# HW_V5_0.net
KiCad netlist of a schematic drawn in Altium Designer
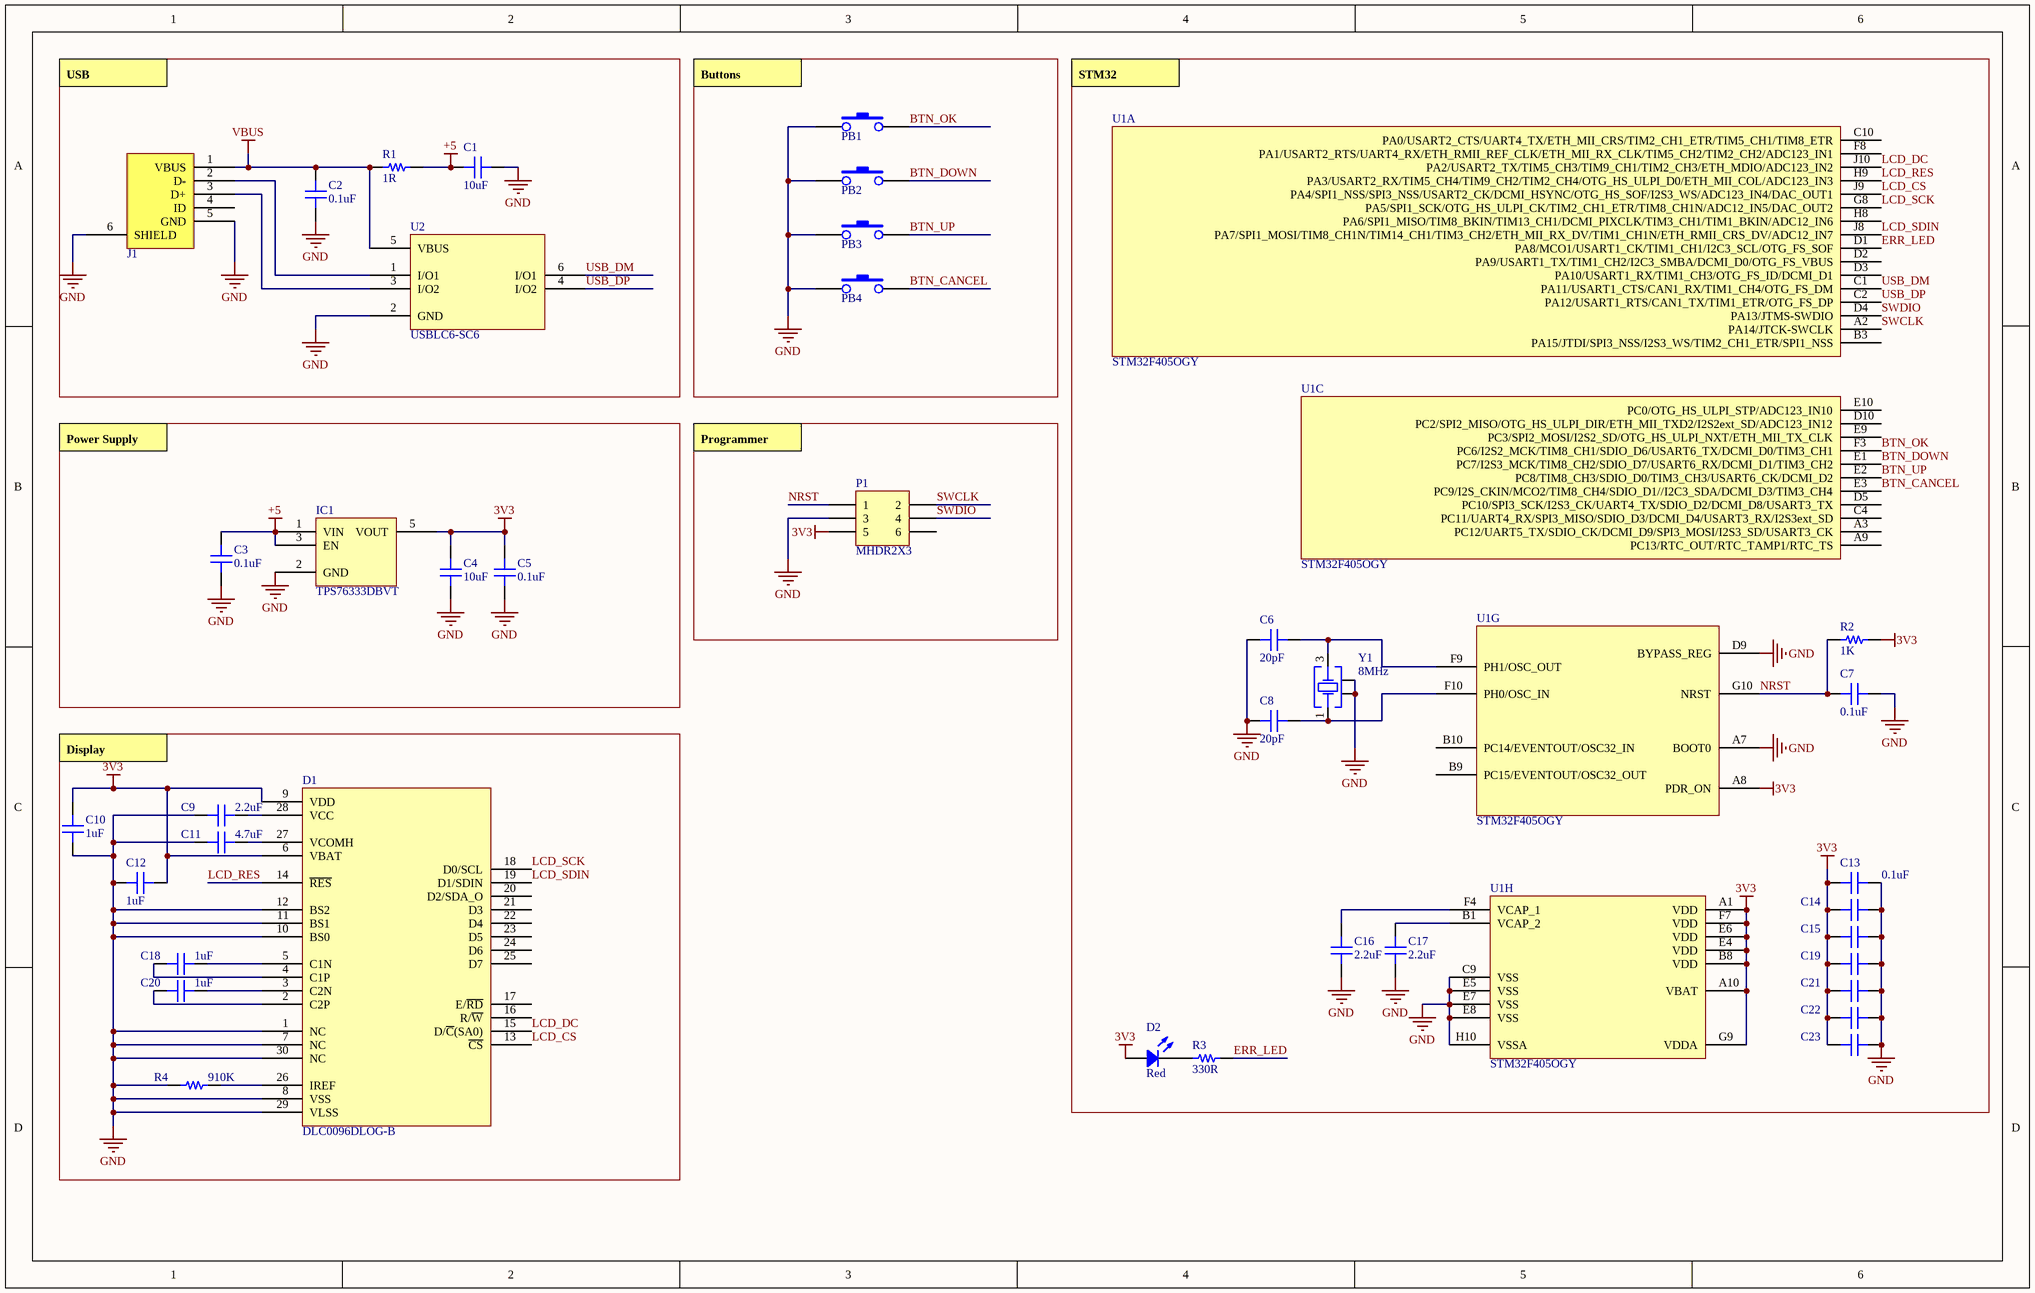
[diagram p0: HW_V5.0.SchDoc]

(export (version "E")
  (design (tool "Eeschema 10.0.6"))
  (components
    (comp (ref "C1")
      (value "10uF")
      (footprint "CAP 0603/1608")
      (description "CAP CER 10UF 6.3V X5R 0603")
      (fields
        (field (name "PART NUMBER") "CL10A106MQ8NNNC")
        (field (name "MANUFACTURER") "Samsung Electro-Mechanics America, Inc.")
      )
      (libsource (lib "Capacitor - Ceramic - Sumsung") (part "CL10A106MQ8NNNC"))
    )
    (comp (ref "C2")
      (value "0.1uF")
      (footprint "CAP 0603/1608")
      (description "CAP CER 0.1UF 16V X7R 0603")
      (fields
        (field (name "PART NUMBER") "CL10B104JO8NNNC")
        (field (name "MANUFACTURER") "Samsung Electro-Mechanics America, Inc.")
      )
      (libsource (lib "Capacitor - Ceramic - Sumsung") (part "CL10B104JO8NNNC"))
    )
    (comp (ref "C3")
      (value "0.1uF")
      (footprint "CAP 0603/1608")
      (description "CAP CER 0.1UF 16V X7R 0603")
      (fields
        (field (name "PART NUMBER") "CL10B104JO8NNNC")
        (field (name "MANUFACTURER") "Samsung Electro-Mechanics America, Inc.")
      )
      (libsource (lib "Capacitor - Ceramic - Sumsung") (part "CL10B104JO8NNNC"))
    )
    (comp (ref "C4")
      (value "10uF")
      (footprint "CAP 0603/1608")
      (description "CAP CER 10UF 6.3V X5R 0603")
      (fields
        (field (name "PART NUMBER") "CL10A106MQ8NNNC")
        (field (name "MANUFACTURER") "Samsung Electro-Mechanics America, Inc.")
      )
      (libsource (lib "Capacitor - Ceramic - Sumsung") (part "CL10A106MQ8NNNC"))
    )
    (comp (ref "C5")
      (value "0.1uF")
      (footprint "CAP 0603/1608")
      (description "CAP CER 0.1UF 16V X7R 0603")
      (fields
        (field (name "PART NUMBER") "CL10B104JO8NNNC")
        (field (name "MANUFACTURER") "Samsung Electro-Mechanics America, Inc.")
      )
      (libsource (lib "Capacitor - Ceramic - Sumsung") (part "CL10B104JO8NNNC"))
    )
    (comp (ref "C6")
      (value "20pF")
      (footprint "CAP 0603/1608")
      (description "CAP CER 20PF 50V NP0 0603")
      (fields
        (field (name "PART NUMBER") "CL10C200JB8NNNC")
        (field (name "MANUFACTURER") "Samsung Electro-Mechanics America, Inc.")
      )
      (libsource (lib "Capacitor - Ceramic - Sumsung") (part "CL10C200JB8NNNC"))
    )
    (comp (ref "C7")
      (value "0.1uF")
      (footprint "CAP 0603/1608")
      (description "CAP CER 0.1UF 16V X7R 0603")
      (fields
        (field (name "PART NUMBER") "CL10B104JO8NNNC")
        (field (name "MANUFACTURER") "Samsung Electro-Mechanics America, Inc.")
      )
      (libsource (lib "Capacitor - Ceramic - Sumsung") (part "CL10B104JO8NNNC"))
    )
    (comp (ref "C8")
      (value "20pF")
      (footprint "CAP 0603/1608")
      (description "CAP CER 20PF 50V NP0 0603")
      (fields
        (field (name "PART NUMBER") "CL10C200JB8NNNC")
        (field (name "MANUFACTURER") "Samsung Electro-Mechanics America, Inc.")
      )
      (libsource (lib "Capacitor - Ceramic - Sumsung") (part "CL10C200JB8NNNC"))
    )
    (comp (ref "C9")
      (value "2.2uF")
      (footprint "CAP 0603/1608")
      (description "CAP CER 2.2UF 16V X5R 0603")
      (fields
        (field (name "PART NUMBER") "CL10A225KO5LNNC")
        (field (name "MANUFACTURER") "Samsung Electro-Mechanics")
      )
      (libsource (lib "Capacitor - Ceramic - Sumsung") (part "CL10A225KO5LNNC"))
    )
    (comp (ref "C10")
      (value "1uF")
      (footprint "CAP 0603/1608")
      (description "CAP CER 1UF 16V X5R 0603")
      (fields
        (field (name "PART NUMBER") "CL10A105KO8NNNC")
        (field (name "MANUFACTURER") "Samsung Electro-Mechanics America, Inc.")
      )
      (libsource (lib "Capacitor - Ceramic - Sumsung") (part "CL10A105KO8NNNC"))
    )
    (comp (ref "C11")
      (value "4.7uF")
      (footprint "CAP 0603/1608")
      (description "CAP CER 4.7UF 16V X5R 0603")
      (fields
        (field (name "PART NUMBER") "CL10A475KO8NNNC")
        (field (name "MANUFACTURER") "Samsung Electro-Mechanics America, Inc.")
      )
      (libsource (lib "Capacitor - Ceramic - Sumsung") (part "CL10A475KO8NNNC"))
    )
    (comp (ref "C12")
      (value "1uF")
      (footprint "CAP 0603/1608")
      (description "CAP CER 1UF 16V X5R 0603")
      (fields
        (field (name "PART NUMBER") "CL10A105KO8NNNC")
        (field (name "MANUFACTURER") "Samsung Electro-Mechanics America, Inc.")
      )
      (libsource (lib "Capacitor - Ceramic - Sumsung") (part "CL10A105KO8NNNC"))
    )
    (comp (ref "C13")
      (value "0.1uF")
      (footprint "CAP 0603/1608")
      (description "CAP CER 0.1UF 16V X7R 0603")
      (fields
        (field (name "PART NUMBER") "CL10B104JO8NNNC")
        (field (name "MANUFACTURER") "Samsung Electro-Mechanics America, Inc.")
      )
      (libsource (lib "Capacitor - Ceramic - Sumsung") (part "CL10B104JO8NNNC"))
    )
    (comp (ref "C14")
      (value "0.1uF")
      (footprint "CAP 0603/1608")
      (description "CAP CER 0.1UF 16V X7R 0603")
      (fields
        (field (name "PART NUMBER") "CL10B104JO8NNNC")
        (field (name "MANUFACTURER") "Samsung Electro-Mechanics America, Inc.")
      )
      (libsource (lib "Capacitor - Ceramic - Sumsung") (part "CL10B104JO8NNNC"))
    )
    (comp (ref "C15")
      (value "0.1uF")
      (footprint "CAP 0603/1608")
      (description "CAP CER 0.1UF 16V X7R 0603")
      (fields
        (field (name "PART NUMBER") "CL10B104JO8NNNC")
        (field (name "MANUFACTURER") "Samsung Electro-Mechanics America, Inc.")
      )
      (libsource (lib "Capacitor - Ceramic - Sumsung") (part "CL10B104JO8NNNC"))
    )
    (comp (ref "C16")
      (value "2.2uF")
      (footprint "CAP 0603/1608")
      (description "CAP CER 2.2UF 16V X5R 0603")
      (fields
        (field (name "PART NUMBER") "CL10A225KO5LNNC")
        (field (name "MANUFACTURER") "Samsung Electro-Mechanics")
      )
      (libsource (lib "Capacitor - Ceramic - Sumsung") (part "CL10A225KO5LNNC"))
    )
    (comp (ref "C17")
      (value "2.2uF")
      (footprint "CAP 0603/1608")
      (description "CAP CER 2.2UF 16V X5R 0603")
      (fields
        (field (name "PART NUMBER") "CL10A225KO5LNNC")
        (field (name "MANUFACTURER") "Samsung Electro-Mechanics")
      )
      (libsource (lib "Capacitor - Ceramic - Sumsung") (part "CL10A225KO5LNNC"))
    )
    (comp (ref "C18")
      (value "1uF")
      (footprint "CAP 0603/1608")
      (description "CAP CER 1UF 25V X5R 0603")
      (fields
        (field (name "PART NUMBER") "CL10A105KA8NNNC")
        (field (name "MANUFACTURER") "Samsung Electro-Mechanics America, Inc.")
      )
      (libsource (lib "Capacitor - Ceramic - Sumsung") (part "CL10A105KA8NNNC"))
    )
    (comp (ref "C19")
      (value "0.1uF")
      (footprint "CAP 0603/1608")
      (description "CAP CER 0.1UF 16V X7R 0603")
      (fields
        (field (name "PART NUMBER") "CL10B104JO8NNNC")
        (field (name "MANUFACTURER") "Samsung Electro-Mechanics America, Inc.")
      )
      (libsource (lib "Capacitor - Ceramic - Sumsung") (part "CL10B104JO8NNNC"))
    )
    (comp (ref "C20")
      (value "1uF")
      (footprint "CAP 0603/1608")
      (description "CAP CER 1UF 25V X5R 0603")
      (fields
        (field (name "PART NUMBER") "CL10A105KA8NNNC")
        (field (name "MANUFACTURER") "Samsung Electro-Mechanics America, Inc.")
      )
      (libsource (lib "Capacitor - Ceramic - Sumsung") (part "CL10A105KA8NNNC"))
    )
    (comp (ref "C21")
      (value "0.1uF")
      (footprint "CAP 0603/1608")
      (description "CAP CER 0.1UF 16V X7R 0603")
      (fields
        (field (name "PART NUMBER") "CL10B104JO8NNNC")
        (field (name "MANUFACTURER") "Samsung Electro-Mechanics America, Inc.")
      )
      (libsource (lib "Capacitor - Ceramic - Sumsung") (part "CL10B104JO8NNNC"))
    )
    (comp (ref "C22")
      (value "0.1uF")
      (footprint "CAP 0603/1608")
      (description "CAP CER 0.1UF 16V X7R 0603")
      (fields
        (field (name "PART NUMBER") "CL10B104JO8NNNC")
        (field (name "MANUFACTURER") "Samsung Electro-Mechanics America, Inc.")
      )
      (libsource (lib "Capacitor - Ceramic - Sumsung") (part "CL10B104JO8NNNC"))
    )
    (comp (ref "C23")
      (value "0.1uF")
      (footprint "CAP 0603/1608")
      (description "CAP CER 0.1UF 16V X7R 0603")
      (fields
        (field (name "PART NUMBER") "CL10B104JO8NNNC")
        (field (name "MANUFACTURER") "Samsung Electro-Mechanics America, Inc.")
      )
      (libsource (lib "Capacitor - Ceramic - Sumsung") (part "CL10B104JO8NNNC"))
    )
    (comp (ref "D1")
      (value "DLC0096DLOG-B")
      (footprint "PMOLED_0096_TOP_CONB")
      (libsource (lib "DISPLAY - PMOLED") (part "DLC0096DLOG-B"))
    )
    (comp (ref "D2")
      (value "Red")
      (footprint "LED 0603/1608 RED")
      (description "LED RED CLEAR 0603 SMD")
      (fields (field (name "PART NUMBER") "LTST-C191KRKT") (field (name "MANUFACTURER") "Lite-On Inc."))
      (libsource (lib "Chip LED") (part "LTST-C191KRKT"))
    )
    (comp (ref "IC1")
      (value "TPS76333DBVT")
      (footprint "TI SOT-23-5 DBV")
      (description "IC REG LDO 3.3V 0.15A SOT23-5")
      (fields (field (name "MANUFACTURER") "Texas Instruments"))
      (libsource (lib "Voltage Regulator - Linear") (part "TPS76333DBVT"))
    )
    (comp (ref "J1")
      (value "U-F-M5DD-W-L")
      (footprint "U-F-M5DD-W-L")
      (description "USB - Micro B Female USB 2 5 5.06*7.59mm USB Connectors")
      (libsource (lib "CONNECTOR - USB") (part "U-F-M5DD-W-L"))
    )
    (comp (ref "P1")
      (value "MHDR2X3")
      (footprint "MHDR2X3")
      (description "Header, 3-Pin, Dual row")
      (fields (field (name "PUBLISHER") "Altium Limited"))
      (libsource (lib "Miscellaneous Connectors") (part "MHDR2X3"))
    )
    (comp (ref "PB1")
      (value "Tactile Switch 3.7 x 3.7")
      (footprint "SW_375_375_4PIN")
      (libsource (lib "BUTTONS - TACTILE") (part "Tactile Switch 3.7 x 3.7"))
    )
    (comp (ref "PB2")
      (value "Tactile Switch 3.7 x 3.7")
      (footprint "SW_375_375_4PIN")
      (libsource (lib "BUTTONS - TACTILE") (part "Tactile Switch 3.7 x 3.7"))
    )
    (comp (ref "PB3")
      (value "Tactile Switch 3.7 x 3.7")
      (footprint "SW_375_375_4PIN")
      (libsource (lib "BUTTONS - TACTILE") (part "Tactile Switch 3.7 x 3.7"))
    )
    (comp (ref "PB4")
      (value "Tactile Switch 3.7 x 3.7")
      (footprint "SW_375_375_4PIN")
      (libsource (lib "BUTTONS - TACTILE") (part "Tactile Switch 3.7 x 3.7"))
    )
    (comp (ref "R1")
      (value "1R")
      (footprint "RES 0603/1608")
      (description "RES SMD 1R OHM 5% 1/8W 0603")
      (fields (field (name "PART NUMBER") "0603S8J010J") (field (name "MANUFACTURER") "Uniohm"))
      (libsource (lib "Resistor - Chip - Uniohm") (part "0603S8J010J"))
    )
    (comp (ref "R2")
      (value "1K")
      (footprint "RES 0603/1608")
      (description "RES SMD 1K OHM 5% 1/8W 0603")
      (fields (field (name "PART NUMBER") "0603S8J0102") (field (name "MANUFACTURER") "Uniohm"))
      (libsource (lib "Resistor - Chip - Uniohm") (part "0603S8J0102"))
    )
    (comp (ref "R3")
      (value "330R")
      (footprint "RES 0603/1608")
      (description "RES SMD 330R OHM 5% 1/8W 0603")
      (fields (field (name "PART NUMBER") "0603S8J0331") (field (name "MANUFACTURER") "Uniohm"))
      (libsource (lib "Resistor - Chip - Uniohm") (part "0603S8J0331"))
    )
    (comp (ref "R4")
      (value "910K")
      (footprint "RES 0603/1608")
      (description "RES SMD 910K OHM 5% 1/8W 0603")
      (fields (field (name "PART NUMBER") "0603S8J0914") (field (name "MANUFACTURER") "Uniohm"))
      (libsource (lib "Resistor - Chip - Uniohm") (part "0603S8J0914"))
    )
    (comp (ref "U1")
      (value "STM32F405OGY")
      (footprint "STM-WLCSP90")
      (description "ARM® Cortex®-M4 series Microcontroller IC 32-Bit 168MHz 1MB (1M x 8) FLASH 90-WLCSP (4.22x3.97)")
      (fields (field (name "MANUFACTURER") "STMicroelectronics"))
      (libsource (lib "ARM - ST - STM32") (part "STM32F405OGY6"))
    )
    (comp (ref "U2")
      (value "USBLC6-SC6")
      (footprint "ST SOT-23-6")
      (description "TVS DIODE 5.25V 17V SOT23-6")
      (fields (field (name "MANUFACTURER") "STMicroelectronics"))
      (libsource (lib "ESD Protection") (part "USBLC6-2"))
    )
    (comp (ref "Y1")
      (value "8MHz")
      (footprint "WE-XTAL_CFPX-180")
      (description "WE-XTAL Quartz Crystal, SMT, CFPX-180, 8MHz, +/-30ppm")
      (fields
        (field (name "MANUFACTURER PART NUMBER") "830108313809")
        (field (name "MANUFACTURER") "Wurth Elektronik")
      )
      (libsource (lib "Altium_WE-XTAL (rev21a)") (part "830108313809"))
    )
  )
  (nets
    (net (code "1") (name "+5") (class "Default")
      (node (ref "C1") (pin "2") (pinfunction "2_2") (pintype "passive"))
      (node (ref "C3") (pin "2") (pinfunction "2_2") (pintype "passive"))
      (node (ref "IC1") (pin "1") (pinfunction "VIN_1") (pintype "passive"))
      (node (ref "IC1") (pin "3") (pinfunction "EN_3") (pintype "passive"))
      (node (ref "R1") (pin "2") (pinfunction "2_2") (pintype "passive"))
    )
    (net (code "2") (name "/BTN_CANCEL") (class "Default")
      (node (ref "PB4") (pin "2") (pinfunction "2_2") (pintype "passive"))
      (node (ref "U1") (pin "E3") (pinfunction "PC9/I2S_CKIN/MCO2/TIM8_CH4/SDIO_D1//I2C3_SDA/DCMI_D3/TIM3_CH4_E3") (pintype "passive"))
    )
    (net (code "3") (name "/BTN_DOWN") (class "Default")
      (node (ref "PB2") (pin "2") (pinfunction "2_2") (pintype "passive"))
      (node (ref "U1") (pin "E1") (pinfunction "PC7/I2S3_MCK/TIM8_CH2/SDIO_D7/USART6_RX/DCMI_D1/TIM3_CH2_E1") (pintype "passive"))
    )
    (net (code "4") (name "/BTN_OK") (class "Default")
      (node (ref "PB1") (pin "2") (pinfunction "2_2") (pintype "passive"))
      (node (ref "U1") (pin "F3") (pinfunction "PC6/I2S2_MCK/TIM8_CH1/SDIO_D6/USART6_TX/DCMI_D0/TIM3_CH1_F3") (pintype "passive"))
    )
    (net (code "5") (name "/BTN_UP") (class "Default")
      (node (ref "PB3") (pin "2") (pinfunction "2_2") (pintype "passive"))
      (node (ref "U1") (pin "E2") (pinfunction "PC8/TIM8_CH3/SDIO_D0/TIM3_CH3/USART6_CK/DCMI_D2_E2") (pintype "passive"))
    )
    (net (code "6") (name "/ERR_LED") (class "Default")
      (node (ref "R3") (pin "2") (pinfunction "2_2") (pintype "passive"))
      (node (ref "U1") (pin "D1") (pinfunction "PA8/MCO1/USART1_CK/TIM1_CH1/I2C3_SCL/OTG_FS_SOF_D1") (pintype "passive"))
    )
    (net (code "7") (name "/LCD_CS") (class "Default")
      (node (ref "D1") (pin "13") (pinfunction "~{CS}_13") (pintype "passive"))
      (node (ref "U1") (pin "J9") (pinfunction "PA4/SPI1_NSS/SPI3_NSS/USART2_CK/DCMI_HSYNC/OTG_HS_SOF/I2S3_WS/ADC123_IN4/DAC_OUT1_J9") (pintype "passive"))
    )
    (net (code "8") (name "/LCD_DC") (class "Default")
      (node (ref "D1") (pin "15") (pinfunction "D/~{C}(SA0)_15") (pintype "passive"))
      (node (ref "U1") (pin "J10") (pinfunction "PA2/USART2_TX/TIM5_CH3/TIM9_CH1/TIM2_CH3/ETH_MDIO/ADC123_IN2_J10") (pintype "passive"))
    )
    (net (code "9") (name "/LCD_RES") (class "Default")
      (node (ref "D1") (pin "14") (pinfunction "~{RES}_14") (pintype "passive"))
      (node (ref "U1") (pin "H9") (pinfunction "PA3/USART2_RX/TIM5_CH4/TIM9_CH2/TIM2_CH4/OTG_HS_ULPI_D0/ETH_MII_COL/ADC123_IN3_H9") (pintype "passive"))
    )
    (net (code "10") (name "/LCD_SCK") (class "Default")
      (node (ref "D1") (pin "18") (pinfunction "D0/SCL_18") (pintype "passive"))
      (node (ref "U1") (pin "G8") (pinfunction "PA5/SPI1_SCK/OTG_HS_ULPI_CK/TIM2_CH1_ETR/TIM8_CH1N/ADC12_IN5/DAC_OUT2_G8") (pintype "passive"))
    )
    (net (code "11") (name "/LCD_SDIN") (class "Default")
      (node (ref "D1") (pin "19") (pinfunction "D1/SDIN_19") (pintype "passive"))
      (node (ref "U1") (pin "J8") (pinfunction "PA7/SPI1_MOSI/TIM8_CH1N/TIM14_CH1/TIM3_CH2/ETH_MII_RX_DV/TIM1_CH1N/ETH_RMII_CRS_DV/ADC12_IN7_J8") (pintype "passive"))
    )
    (net (code "12") (name "/NRST") (class "Default")
      (node (ref "C7") (pin "2") (pinfunction "2_2") (pintype "passive"))
      (node (ref "P1") (pin "1") (pinfunction "1_1") (pintype "passive"))
      (node (ref "R2") (pin "1") (pinfunction "1_1") (pintype "passive"))
      (node (ref "U1") (pin "G10") (pinfunction "NRST_G10") (pintype "passive"))
    )
    (net (code "13") (name "/SWCLK") (class "Default")
      (node (ref "P1") (pin "2") (pinfunction "2_2") (pintype "passive"))
      (node (ref "U1") (pin "A2") (pinfunction "PA14/JTCK-SWCLK_A2") (pintype "passive"))
    )
    (net (code "14") (name "/SWDIO") (class "Default")
      (node (ref "P1") (pin "4") (pinfunction "4_4") (pintype "passive"))
      (node (ref "U1") (pin "D4") (pinfunction "PA13/JTMS-SWDIO_D4") (pintype "passive"))
    )
    (net (code "15") (name "/USB_DM") (class "Default")
      (node (ref "U1") (pin "C1") (pinfunction "PA11/USART1_CTS/CAN1_RX/TIM1_CH4/OTG_FS_DM_C1") (pintype "passive"))
      (node (ref "U2") (pin "6") (pinfunction "I/O1_6") (pintype "passive"))
    )
    (net (code "16") (name "/USB_DP") (class "Default")
      (node (ref "U1") (pin "C2") (pinfunction "PA12/USART1_RTS/CAN1_TX/TIM1_ETR/OTG_FS_DP_C2") (pintype "passive"))
      (node (ref "U2") (pin "4") (pinfunction "I/O2_4") (pintype "passive"))
    )
    (net (code "17") (name "3V3") (class "Default")
      (node (ref "C10") (pin "2") (pinfunction "2_2") (pintype "passive"))
      (node (ref "C12") (pin "1") (pinfunction "1_1") (pintype "passive"))
      (node (ref "C13") (pin "2") (pinfunction "2_2") (pintype "passive"))
      (node (ref "C14") (pin "2") (pinfunction "2_2") (pintype "passive"))
      (node (ref "C15") (pin "2") (pinfunction "2_2") (pintype "passive"))
      (node (ref "C19") (pin "2") (pinfunction "2_2") (pintype "passive"))
      (node (ref "C21") (pin "2") (pinfunction "2_2") (pintype "passive"))
      (node (ref "C22") (pin "2") (pinfunction "2_2") (pintype "passive"))
      (node (ref "C23") (pin "2") (pinfunction "2_2") (pintype "passive"))
      (node (ref "C4") (pin "2") (pinfunction "2_2") (pintype "passive"))
      (node (ref "C5") (pin "2") (pinfunction "2_2") (pintype "passive"))
      (node (ref "D1") (pin "6") (pinfunction "VBAT_6") (pintype "passive"))
      (node (ref "D1") (pin "9") (pinfunction "VDD_9") (pintype "passive"))
      (node (ref "D2") (pin "1") (pinfunction "1_1") (pintype "passive"))
      (node (ref "IC1") (pin "5") (pinfunction "VOUT_5") (pintype "passive"))
      (node (ref "P1") (pin "5") (pinfunction "5_5") (pintype "passive"))
      (node (ref "R2") (pin "2") (pinfunction "2_2") (pintype "passive"))
      (node (ref "U1") (pin "A1") (pinfunction "VDD_A1") (pintype "passive"))
      (node (ref "U1") (pin "A10") (pinfunction "VBAT_A10") (pintype "passive"))
      (node (ref "U1") (pin "A8") (pinfunction "PDR_ON_A8") (pintype "passive"))
      (node (ref "U1") (pin "B8") (pinfunction "VDD_B8") (pintype "passive"))
      (node (ref "U1") (pin "E4") (pinfunction "VDD_E4") (pintype "passive"))
      (node (ref "U1") (pin "E6") (pinfunction "VDD_E6") (pintype "passive"))
      (node (ref "U1") (pin "F7") (pinfunction "VDD_F7") (pintype "passive"))
      (node (ref "U1") (pin "G9") (pinfunction "VDDA_G9") (pintype "passive"))
    )
    (net (code "18") (name "GND") (class "Default")
      (node (ref "C1") (pin "1") (pinfunction "1_1") (pintype "passive"))
      (node (ref "C10") (pin "1") (pinfunction "1_1") (pintype "passive"))
      (node (ref "C11") (pin "1") (pinfunction "1_1") (pintype "passive"))
      (node (ref "C12") (pin "2") (pinfunction "2_2") (pintype "passive"))
      (node (ref "C13") (pin "1") (pinfunction "1_1") (pintype "passive"))
      (node (ref "C14") (pin "1") (pinfunction "1_1") (pintype "passive"))
      (node (ref "C15") (pin "1") (pinfunction "1_1") (pintype "passive"))
      (node (ref "C16") (pin "1") (pinfunction "1_1") (pintype "passive"))
      (node (ref "C17") (pin "1") (pinfunction "1_1") (pintype "passive"))
      (node (ref "C19") (pin "1") (pinfunction "1_1") (pintype "passive"))
      (node (ref "C2") (pin "1") (pinfunction "1_1") (pintype "passive"))
      (node (ref "C21") (pin "1") (pinfunction "1_1") (pintype "passive"))
      (node (ref "C22") (pin "1") (pinfunction "1_1") (pintype "passive"))
      (node (ref "C23") (pin "1") (pinfunction "1_1") (pintype "passive"))
      (node (ref "C3") (pin "1") (pinfunction "1_1") (pintype "passive"))
      (node (ref "C4") (pin "1") (pinfunction "1_1") (pintype "passive"))
      (node (ref "C5") (pin "1") (pinfunction "1_1") (pintype "passive"))
      (node (ref "C6") (pin "1") (pinfunction "1_1") (pintype "passive"))
      (node (ref "C7") (pin "1") (pinfunction "1_1") (pintype "passive"))
      (node (ref "C8") (pin "1") (pinfunction "1_1") (pintype "passive"))
      (node (ref "C9") (pin "2") (pinfunction "2_2") (pintype "passive"))
      (node (ref "D1") (pin "1") (pinfunction "NC_1") (pintype "passive"))
      (node (ref "D1") (pin "10") (pinfunction "BS0_10") (pintype "passive"))
      (node (ref "D1") (pin "11") (pinfunction "BS1_11") (pintype "passive"))
      (node (ref "D1") (pin "12") (pinfunction "BS2_12") (pintype "passive"))
      (node (ref "D1") (pin "29") (pinfunction "VLSS_29") (pintype "passive"))
      (node (ref "D1") (pin "30") (pinfunction "NC_30") (pintype "passive"))
      (node (ref "D1") (pin "7") (pinfunction "NC_7") (pintype "passive"))
      (node (ref "D1") (pin "8") (pinfunction "VSS_8") (pintype "passive"))
      (node (ref "IC1") (pin "2") (pinfunction "GND_2") (pintype "passive"))
      (node (ref "J1") (pin "5") (pinfunction "GND_5") (pintype "passive"))
      (node (ref "J1") (pin "6") (pinfunction "SHIELD_6") (pintype "passive"))
      (node (ref "P1") (pin "3") (pinfunction "3_3") (pintype "passive"))
      (node (ref "PB1") (pin "1") (pinfunction "1_1") (pintype "passive"))
      (node (ref "PB2") (pin "1") (pinfunction "1_1") (pintype "passive"))
      (node (ref "PB3") (pin "1") (pinfunction "1_1") (pintype "passive"))
      (node (ref "PB4") (pin "1") (pinfunction "1_1") (pintype "passive"))
      (node (ref "R4") (pin "1") (pinfunction "1_1") (pintype "passive"))
      (node (ref "U1") (pin "A7") (pinfunction "BOOT0_A7") (pintype "passive"))
      (node (ref "U1") (pin "C9") (pinfunction "VSS_C9") (pintype "passive"))
      (node (ref "U1") (pin "D9") (pinfunction "BYPASS_REG_D9") (pintype "passive"))
      (node (ref "U1") (pin "E5") (pinfunction "VSS_E5") (pintype "passive"))
      (node (ref "U1") (pin "E7") (pinfunction "VSS_E7") (pintype "passive"))
      (node (ref "U1") (pin "E8") (pinfunction "VSS_E8") (pintype "passive"))
      (node (ref "U1") (pin "H10") (pinfunction "VSSA_H10") (pintype "passive"))
      (node (ref "U2") (pin "2") (pinfunction "GND_2") (pintype "passive"))
      (node (ref "Y1") (pin "2") (pinfunction "GND&Lid_2") (pintype "passive"))
      (node (ref "Y1") (pin "4") (pinfunction "GND&Lid_4") (pintype "passive"))
    )
    (net (code "19") (name "Net-(D1-C1N)") (class "Default")
      (node (ref "C18") (pin "2") (pinfunction "2_2") (pintype "passive"))
      (node (ref "D1") (pin "5") (pinfunction "C1N_5") (pintype "passive"))
    )
    (net (code "20") (name "Net-(D1-C1P)") (class "Default")
      (node (ref "C18") (pin "1") (pinfunction "1_1") (pintype "passive"))
      (node (ref "D1") (pin "4") (pinfunction "C1P_4") (pintype "passive"))
    )
    (net (code "21") (name "Net-(D1-C2N)") (class "Default")
      (node (ref "C20") (pin "2") (pinfunction "2_2") (pintype "passive"))
      (node (ref "D1") (pin "3") (pinfunction "C2N_3") (pintype "passive"))
    )
    (net (code "22") (name "Net-(D1-C2P)") (class "Default")
      (node (ref "C20") (pin "1") (pinfunction "1_1") (pintype "passive"))
      (node (ref "D1") (pin "2") (pinfunction "C2P_2") (pintype "passive"))
    )
    (net (code "23") (name "Net-(D1-IREF)") (class "Default")
      (node (ref "D1") (pin "26") (pinfunction "IREF_26") (pintype "passive"))
      (node (ref "R4") (pin "2") (pinfunction "2_2") (pintype "passive"))
    )
    (net (code "24") (name "Net-(D1-VCC)") (class "Default")
      (node (ref "C9") (pin "1") (pinfunction "1_1") (pintype "passive"))
      (node (ref "D1") (pin "28") (pinfunction "VCC_28") (pintype "passive"))
    )
    (net (code "25") (name "Net-(D1-VCOMH)") (class "Default")
      (node (ref "C11") (pin "2") (pinfunction "2_2") (pintype "passive"))
      (node (ref "D1") (pin "27") (pinfunction "VCOMH_27") (pintype "passive"))
    )
    (net (code "26") (name "Net-(D2-Pad2)") (class "Default")
      (node (ref "D2") (pin "2") (pinfunction "2_2") (pintype "passive"))
      (node (ref "R3") (pin "1") (pinfunction "1_1") (pintype "passive"))
    )
    (net (code "27") (name "Net-(J1-D+)") (class "Default")
      (node (ref "J1") (pin "3") (pinfunction "D+_3") (pintype "passive"))
      (node (ref "U2") (pin "3") (pinfunction "I/O2_3") (pintype "passive"))
    )
    (net (code "28") (name "Net-(J1-D-)") (class "Default")
      (node (ref "J1") (pin "2") (pinfunction "D-_2") (pintype "passive"))
      (node (ref "U2") (pin "1") (pinfunction "I/O1_1") (pintype "passive"))
    )
    (net (code "29") (name "Net-(U1G-PH0{slash}OSC_IN)") (class "Default")
      (node (ref "C8") (pin "2") (pinfunction "2_2") (pintype "passive"))
      (node (ref "U1") (pin "F10") (pinfunction "PH0/OSC_IN_F10") (pintype "passive"))
      (node (ref "Y1") (pin "1") (pinfunction "Crystal_1") (pintype "passive"))
    )
    (net (code "30") (name "Net-(U1G-PH1{slash}OSC_OUT)") (class "Default")
      (node (ref "C6") (pin "2") (pinfunction "2_2") (pintype "passive"))
      (node (ref "U1") (pin "F9") (pinfunction "PH1/OSC_OUT_F9") (pintype "passive"))
      (node (ref "Y1") (pin "3") (pinfunction "Crystal_3") (pintype "passive"))
    )
    (net (code "31") (name "Net-(U1H-VCAP_1)") (class "Default")
      (node (ref "C16") (pin "2") (pinfunction "2_2") (pintype "passive"))
      (node (ref "U1") (pin "F4") (pinfunction "VCAP_1_F4") (pintype "passive"))
    )
    (net (code "32") (name "Net-(U1H-VCAP_2)") (class "Default")
      (node (ref "C17") (pin "2") (pinfunction "2_2") (pintype "passive"))
      (node (ref "U1") (pin "B1") (pinfunction "VCAP_2_B1") (pintype "passive"))
    )
    (net (code "33") (name "VBUS") (class "Default")
      (node (ref "C2") (pin "2") (pinfunction "2_2") (pintype "passive"))
      (node (ref "J1") (pin "1") (pinfunction "VBUS_1") (pintype "passive"))
      (node (ref "R1") (pin "1") (pinfunction "1_1") (pintype "passive"))
      (node (ref "U2") (pin "5") (pinfunction "VBUS_5") (pintype "passive"))
    )
    (net (code "34") (name "unconnected-(D1-D2{slash}SDA_O-Pad20)") (class "Default")
      (node (ref "D1") (pin "20") (pinfunction "D2/SDA_O_20") (pintype "passive"))
    )
    (net (code "35") (name "unconnected-(D1-D3-Pad21)") (class "Default")
      (node (ref "D1") (pin "21") (pinfunction "D3_21") (pintype "passive"))
    )
    (net (code "36") (name "unconnected-(D1-D4-Pad22)") (class "Default")
      (node (ref "D1") (pin "22") (pinfunction "D4_22") (pintype "passive"))
    )
    (net (code "37") (name "unconnected-(D1-D5-Pad23)") (class "Default")
      (node (ref "D1") (pin "23") (pinfunction "D5_23") (pintype "passive"))
    )
    (net (code "38") (name "unconnected-(D1-D6-Pad24)") (class "Default")
      (node (ref "D1") (pin "24") (pinfunction "D6_24") (pintype "passive"))
    )
    (net (code "39") (name "unconnected-(D1-D7-Pad25)") (class "Default")
      (node (ref "D1") (pin "25") (pinfunction "D7_25") (pintype "passive"))
    )
    (net (code "40") (name "unconnected-(D1-E{slash}~{RD}-Pad17)") (class "Default")
      (node (ref "D1") (pin "17") (pinfunction "E/~{RD}_17") (pintype "passive"))
    )
    (net (code "41") (name "unconnected-(D1-R{slash}~{W}-Pad16)") (class "Default")
      (node (ref "D1") (pin "16") (pinfunction "R/~{W}_16") (pintype "passive"))
    )
    (net (code "42") (name "unconnected-(J1-ID-Pad4)") (class "Default")
      (node (ref "J1") (pin "4") (pinfunction "ID_4") (pintype "passive"))
    )
    (net (code "43") (name "unconnected-(P1-Pad6)") (class "Default")
      (node (ref "P1") (pin "6") (pinfunction "6_6") (pintype "passive"))
    )
    (net (code "44") (name "unconnected-(U1A-PA0{slash}USART2_CTS{slash}UART4_TX{slash}ETH_MII_CRS{slash}TIM2_CH1_ETR{slash}TIM5_CH1{slash}TIM8_ETR-PadC10)") (class "Default")
      (node (ref "U1") (pin "C10") (pinfunction "PA0/USART2_CTS/UART4_TX/ETH_MII_CRS/TIM2_CH1_ETR/TIM5_CH1/TIM8_ETR_C10") (pintype "passive"))
    )
    (net (code "45") (name "unconnected-(U1A-PA1{slash}USART2_RTS{slash}UART4_RX{slash}ETH_RMII_REF_CLK{slash}ETH_MII_RX_CLK{slash}TIM5_CH2{slash}TIM2_CH2{slash}ADC123_IN1-PadF8)") (class "Default")
      (node (ref "U1") (pin "F8") (pinfunction "PA1/USART2_RTS/UART4_RX/ETH_RMII_REF_CLK/ETH_MII_RX_CLK/TIM5_CH2/TIM2_CH2/ADC123_IN1_F8") (pintype "passive"))
    )
    (net (code "46") (name "unconnected-(U1A-PA6{slash}SPI1_MISO{slash}TIM8_BKIN{slash}TIM13_CH1{slash}DCMI_PIXCLK{slash}TIM3_CH1{slash}TIM1_BKIN{slash}ADC12_IN6-PadH8)") (class "Default")
      (node (ref "U1") (pin "H8") (pinfunction "PA6/SPI1_MISO/TIM8_BKIN/TIM13_CH1/DCMI_PIXCLK/TIM3_CH1/TIM1_BKIN/ADC12_IN6_H8") (pintype "passive"))
    )
    (net (code "47") (name "unconnected-(U1A-PA9{slash}USART1_TX{slash}TIM1_CH2{slash}I2C3_SMBA{slash}DCMI_D0{slash}OTG_FS_VBUS-PadD2)") (class "Default")
      (node (ref "U1") (pin "D2") (pinfunction "PA9/USART1_TX/TIM1_CH2/I2C3_SMBA/DCMI_D0/OTG_FS_VBUS_D2") (pintype "passive"))
    )
    (net (code "48") (name "unconnected-(U1A-PA10{slash}USART1_RX{slash}TIM1_CH3{slash}OTG_FS_ID{slash}DCMI_D1-PadD3)") (class "Default")
      (node (ref "U1") (pin "D3") (pinfunction "PA10/USART1_RX/TIM1_CH3/OTG_FS_ID/DCMI_D1_D3") (pintype "passive"))
    )
    (net (code "49") (name "unconnected-(U1A-PA15{slash}JTDI{slash}SPI3_NSS{slash}I2S3_WS{slash}TIM2_CH1_ETR{slash}SPI1_NSS-PadB3)") (class "Default")
      (node (ref "U1") (pin "B3") (pinfunction "PA15/JTDI/SPI3_NSS/I2S3_WS/TIM2_CH1_ETR/SPI1_NSS_B3") (pintype "passive"))
    )
    (net (code "50") (name "unconnected-(U1C-PC0{slash}OTG_HS_ULPI_STP{slash}ADC123_IN10-PadE10)") (class "Default")
      (node (ref "U1") (pin "E10") (pinfunction "PC0/OTG_HS_ULPI_STP/ADC123_IN10_E10") (pintype "passive"))
    )
    (net (code "51") (name "unconnected-(U1C-PC2{slash}SPI2_MISO{slash}OTG_HS_ULPI_DIR{slash}ETH_MII_TXD2{slash}I2S2ext_SD{slash}ADC123_IN12-PadD10)") (class "Default")
      (node (ref "U1") (pin "D10") (pinfunction "PC2/SPI2_MISO/OTG_HS_ULPI_DIR/ETH_MII_TXD2/I2S2ext_SD/ADC123_IN12_D10") (pintype "passive"))
    )
    (net (code "52") (name "unconnected-(U1C-PC3{slash}SPI2_MOSI{slash}I2S2_SD{slash}OTG_HS_ULPI_NXT{slash}ETH_MII_TX_CLK-PadE9)") (class "Default")
      (node (ref "U1") (pin "E9") (pinfunction "PC3/SPI2_MOSI/I2S2_SD/OTG_HS_ULPI_NXT/ETH_MII_TX_CLK_E9") (pintype "passive"))
    )
    (net (code "53") (name "unconnected-(U1C-PC10{slash}SPI3_SCK{slash}I2S3_CK{slash}UART4_TX{slash}SDIO_D2{slash}DCMI_D8{slash}USART3_TX-PadD5)") (class "Default")
      (node (ref "U1") (pin "D5") (pinfunction "PC10/SPI3_SCK/I2S3_CK/UART4_TX/SDIO_D2/DCMI_D8/USART3_TX_D5") (pintype "passive"))
    )
    (net (code "54") (name "unconnected-(U1C-PC11{slash}UART4_RX{slash}SPI3_MISO{slash}SDIO_D3{slash}DCMI_D4{slash}USART3_RX{slash}I2S3ext_SD-PadC4)") (class "Default")
      (node (ref "U1") (pin "C4") (pinfunction "PC11/UART4_RX/SPI3_MISO/SDIO_D3/DCMI_D4/USART3_RX/I2S3ext_SD_C4") (pintype "passive"))
    )
    (net (code "55") (name "unconnected-(U1C-PC12{slash}UART5_TX{slash}SDIO_CK{slash}DCMI_D9{slash}SPI3_MOSI{slash}I2S3_SD{slash}USART3_CK-PadA3)") (class "Default")
      (node (ref "U1") (pin "A3") (pinfunction "PC12/UART5_TX/SDIO_CK/DCMI_D9/SPI3_MOSI/I2S3_SD/USART3_CK_A3") (pintype "passive"))
    )
    (net (code "56") (name "unconnected-(U1C-PC13{slash}RTC_OUT{slash}RTC_TAMP1{slash}RTC_TS-PadA9)") (class "Default")
      (node (ref "U1") (pin "A9") (pinfunction "PC13/RTC_OUT/RTC_TAMP1/RTC_TS_A9") (pintype "passive"))
    )
    (net (code "57") (name "unconnected-(U1G-PC14{slash}EVENTOUT{slash}OSC32_IN-PadB10)") (class "Default")
      (node (ref "U1") (pin "B10") (pinfunction "PC14/EVENTOUT/OSC32_IN_B10") (pintype "passive"))
    )
    (net (code "58") (name "unconnected-(U1G-PC15{slash}EVENTOUT{slash}OSC32_OUT-PadB9)") (class "Default")
      (node (ref "U1") (pin "B9") (pinfunction "PC15/EVENTOUT/OSC32_OUT_B9") (pintype "passive"))
    )
  )
)
